# DC28_Jack-Attack_Badge-1.net
KiCad netlist of a schematic drawn in EAGLE
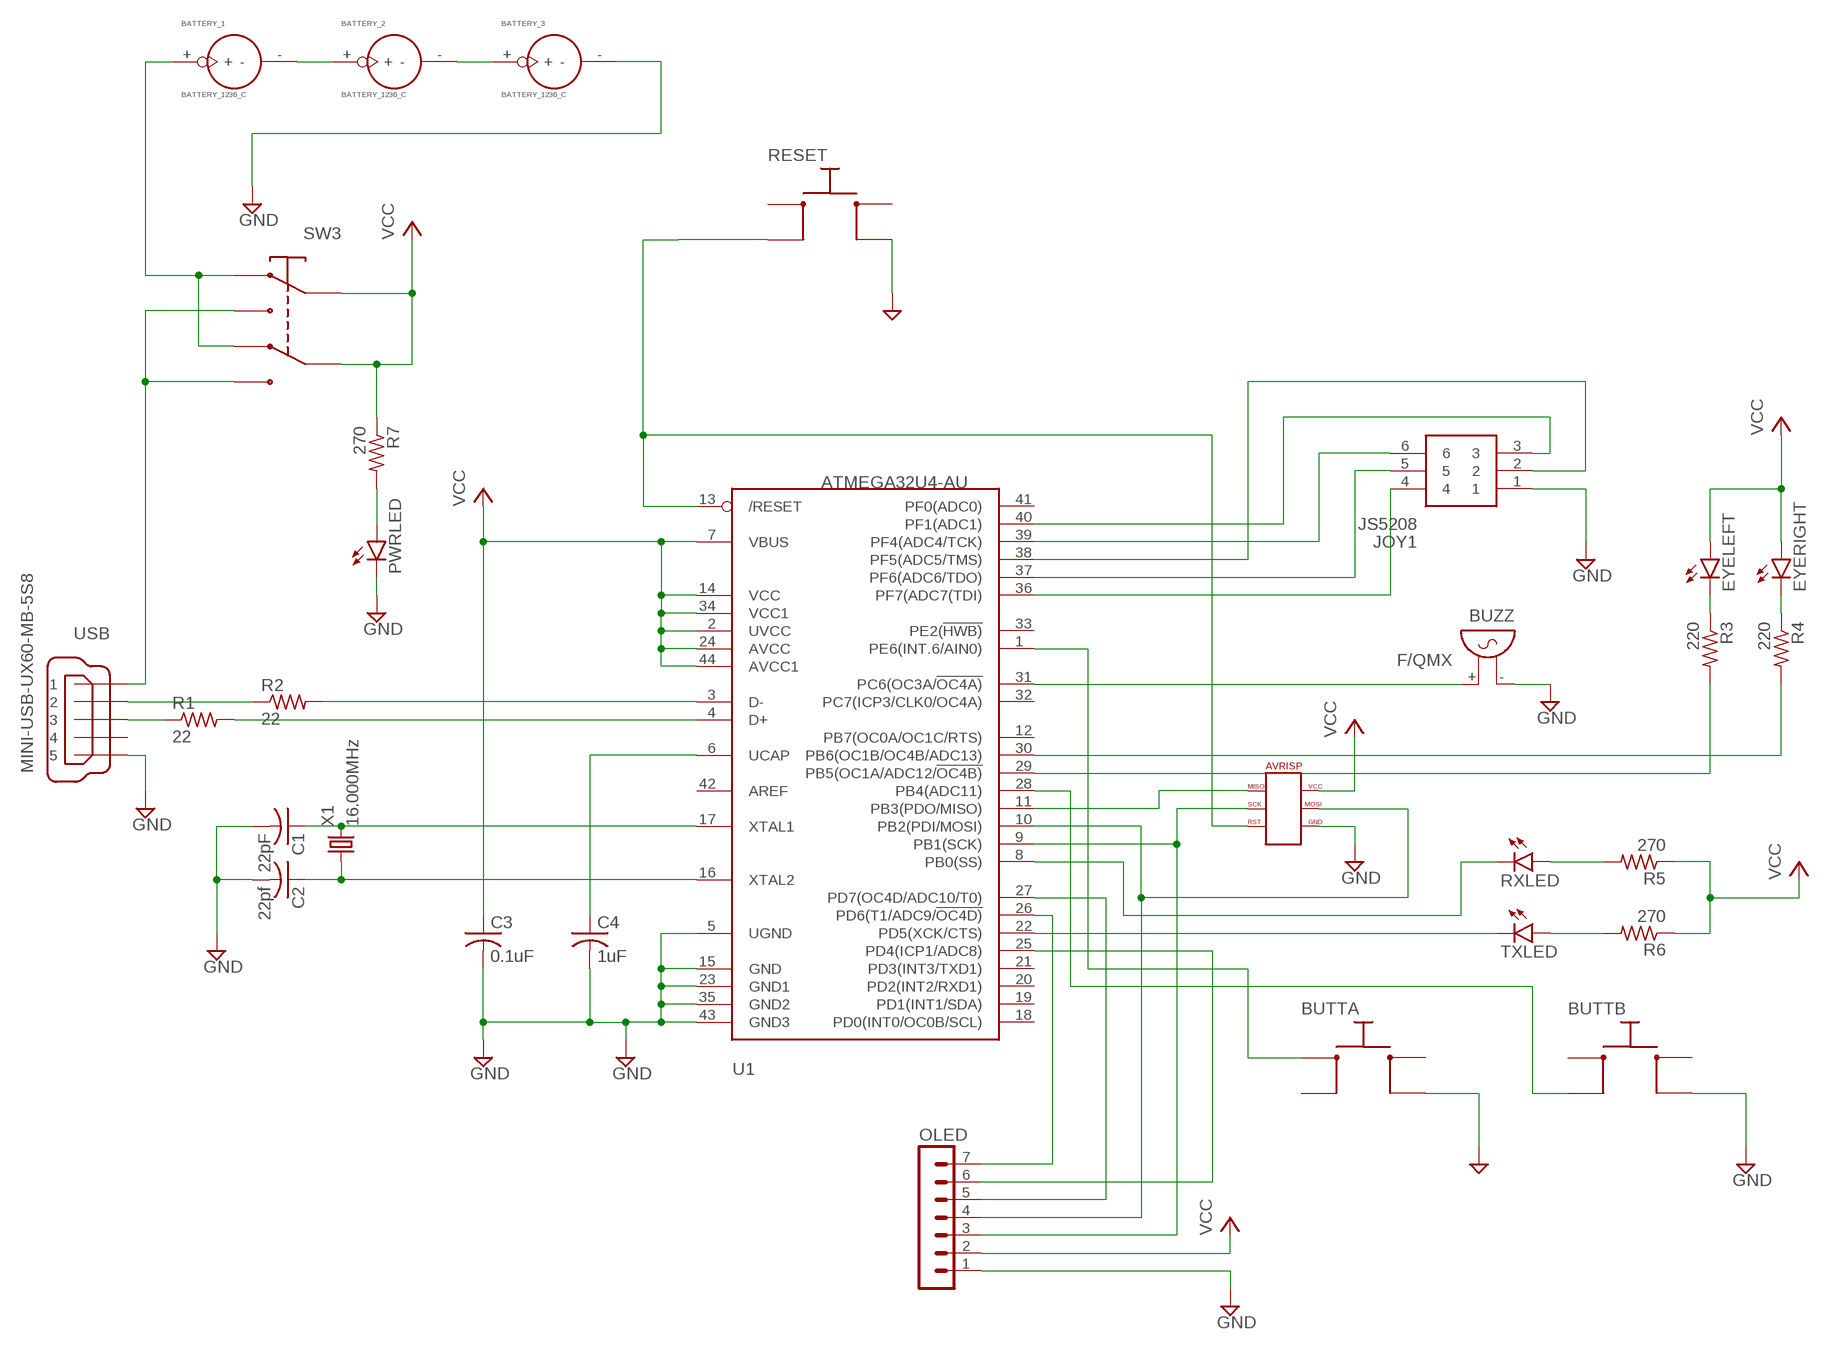
[diagram p0: schematic, sheet 1]

(export (version "E")
  (design (tool "Eeschema 10.0.6"))
  (components
    (comp (ref "BATTERY_1")
      (value "BATTERY_1236_C")
      (footprint "eagle-import:BATTERY_1236_C")
      (libsource (lib "eagle-import") (part "BATTERY_1236_C"))
    )
    (comp (ref "BATTERY_2")
      (value "BATTERY_1236_C")
      (footprint "eagle-import:BATTERY_1236_C")
      (libsource (lib "eagle-import") (part "BATTERY_1236_C"))
    )
    (comp (ref "BATTERY_3")
      (value "BATTERY_1236_C")
      (footprint "eagle-import:BATTERY_1236_C")
      (libsource (lib "eagle-import") (part "BATTERY_1236_C"))
    )
    (comp (ref "BUTTA")
      (value "PTS645")
      (footprint "eagle-import:PTS645_SMD")
      (libsource (lib "eagle-import") (part "PTS645"))
    )
    (comp (ref "BUTTB")
      (value "PTS645")
      (footprint "eagle-import:PTS645_SMD")
      (libsource (lib "eagle-import") (part "PTS645"))
    )
    (comp (ref "BUZZ")
      (value "F/QMX")
      (footprint "eagle-import:F_QMX")
      (libsource (lib "eagle-import") (part "F/QMX"))
    )
    (comp (ref "C1")
      (value "22pF")
      (footprint "eagle-import:C0805")
      (libsource (lib "eagle-import") (part "C-USC0805"))
    )
    (comp (ref "C2")
      (value "22pf")
      (footprint "eagle-import:C0805")
      (libsource (lib "eagle-import") (part "C-USC0805"))
    )
    (comp (ref "C3")
      (value "0.1uF")
      (footprint "eagle-import:C0805")
      (libsource (lib "eagle-import") (part "C-USC0805"))
    )
    (comp (ref "C4")
      (value "1uF")
      (footprint "eagle-import:C0805")
      (libsource (lib "eagle-import") (part "C-USC0805"))
    )
    (comp (ref "EYELEFT")
      (value "LED5MM")
      (footprint "eagle-import:LED5MM")
      (libsource (lib "eagle-import") (part "LED5MM"))
    )
    (comp (ref "EYERIGHT")
      (value "LED5MM")
      (footprint "eagle-import:LED5MM")
      (libsource (lib "eagle-import") (part "LED5MM"))
    )
    (comp (ref "JOY1")
      (value "JS5208")
      (footprint "eagle-import:JS5208")
      (fields (field (name "MOUSER_PART_NUMBER") "612-JS5208"))
      (libsource (lib "eagle-import") (part "JS5208"))
    )
    (comp (ref "OLED")
      (value "MA07-1")
      (footprint "eagle-import:MA07-1")
      (libsource (lib "eagle-import") (part "MA07-1"))
    )
    (comp (ref "PWRLED")
      (value "LEDCHIP-LED0805")
      (footprint "eagle-import:CHIP-LED0805")
      (libsource (lib "eagle-import") (part "LEDCHIP-LED0805"))
    )
    (comp (ref "R1")
      (value "22")
      (footprint "eagle-import:R0805")
      (libsource (lib "eagle-import") (part "R-US_R0805"))
    )
    (comp (ref "R2")
      (value "22")
      (footprint "eagle-import:R0805")
      (libsource (lib "eagle-import") (part "R-US_R0805"))
    )
    (comp (ref "R3")
      (value "220")
      (footprint "eagle-import:R0805")
      (libsource (lib "eagle-import") (part "R-US_R0805"))
    )
    (comp (ref "R4")
      (value "220")
      (footprint "eagle-import:R0805")
      (libsource (lib "eagle-import") (part "R-US_R0805"))
    )
    (comp (ref "R5")
      (value "270")
      (footprint "eagle-import:R0805")
      (libsource (lib "eagle-import") (part "R-US_R0805"))
    )
    (comp (ref "R6")
      (value "270")
      (footprint "eagle-import:R0805")
      (libsource (lib "eagle-import") (part "R-US_R0805"))
    )
    (comp (ref "R7")
      (value "270")
      (footprint "eagle-import:R0805")
      (libsource (lib "eagle-import") (part "R-US_R0805"))
    )
    (comp (ref "RESET")
      (value "PTS645")
      (footprint "eagle-import:PTS645_SMD")
      (libsource (lib "eagle-import") (part "PTS645"))
    )
    (comp (ref "RXLED")
      (value "LEDCHIP-LED0805")
      (footprint "eagle-import:CHIP-LED0805")
      (libsource (lib "eagle-import") (part "LEDCHIP-LED0805"))
    )
    (comp (ref "SW3")
      (value "JS202011AQN")
      (footprint "eagle-import:JS202011AQN")
      (libsource (lib "eagle-import") (part "JS202011AQN"))
    )
    (comp (ref "TXLED")
      (value "LEDCHIP-LED0805")
      (footprint "eagle-import:CHIP-LED0805")
      (libsource (lib "eagle-import") (part "LEDCHIP-LED0805"))
    )
    (comp (ref "U$1")
      (value "AVRISP_POGO")
      (footprint "eagle-import:AVRISP_POGO")
      (libsource (lib "eagle-import") (part "AVRISP_POGO"))
    )
    (comp (ref "U1")
      (value "ATMEGA32U4-AU")
      (footprint "eagle-import:TQFP44")
      (libsource (lib "eagle-import") (part "ATMEGA32U4-AU"))
    )
    (comp (ref "USB")
      (value "MINI-USB-UX60-MB-5S8")
      (footprint "eagle-import:UX60-MB-5S8")
      (libsource (lib "eagle-import") (part "MINI-USB-UX60-MB-5S8"))
    )
    (comp (ref "X1")
      (value "16.000MHz")
      (footprint "eagle-import:CSM-7X-DU")
      (libsource (lib "eagle-import") (part "CSM-7X-DU"))
    )
  )
  (nets
    (net (code "1") (name "GND") (class "Default")
      (node (ref "BATTERY_3") (pin "-") (pinfunction "-_-") (pintype "bidirectional"))
      (node (ref "BUTTA") (pin "P$4") (pinfunction "4_P$4") (pintype "bidirectional"))
      (node (ref "BUTTB") (pin "P$4") (pinfunction "4_P$4") (pintype "bidirectional"))
      (node (ref "BUZZ") (pin "-") (pinfunction "1_-") (pintype "passive"))
      (node (ref "C1") (pin "2") (pinfunction "2_2") (pintype "passive"))
      (node (ref "C2") (pin "2") (pinfunction "2_2") (pintype "passive"))
      (node (ref "C3") (pin "2") (pinfunction "2_2") (pintype "passive"))
      (node (ref "C4") (pin "2") (pinfunction "2_2") (pintype "passive"))
      (node (ref "JOY1") (pin "1") (pinfunction "1_1") (pintype "bidirectional"))
      (node (ref "OLED") (pin "1") (pinfunction "1_1") (pintype "passive"))
      (node (ref "PWRLED") (pin "C") (pinfunction "C_C") (pintype "passive"))
      (node (ref "RESET") (pin "P$4") (pinfunction "4_P$4") (pintype "bidirectional"))
      (node (ref "U$1") (pin "P$6") (pinfunction "P$6_P$6") (pintype "bidirectional"))
      (node (ref "U$1") (pin "P$6B") (pinfunction "P$6_P$6B") (pintype "bidirectional"))
      (node (ref "U1") (pin "15") (pinfunction "GND_15") (pintype "bidirectional"))
      (node (ref "U1") (pin "23") (pinfunction "GND1_23") (pintype "bidirectional"))
      (node (ref "U1") (pin "35") (pinfunction "GND2_35") (pintype "bidirectional"))
      (node (ref "U1") (pin "43") (pinfunction "GND3_43") (pintype "bidirectional"))
      (node (ref "U1") (pin "5") (pinfunction "UGND_5") (pintype "bidirectional"))
      (node (ref "USB") (pin "5") (pinfunction "5_5") (pintype "input"))
    )
    (net (code "2") (name "Net-(BATTERY_1-Pad-)") (class "Default")
      (node (ref "BATTERY_1") (pin "-") (pinfunction "-_-") (pintype "bidirectional"))
      (node (ref "BATTERY_2") (pin "+") (pinfunction "+_+") (pintype "bidirectional"))
    )
    (net (code "3") (name "Net-(BATTERY_2-Pad-)") (class "Default")
      (node (ref "BATTERY_2") (pin "-") (pinfunction "-_-") (pintype "bidirectional"))
      (node (ref "BATTERY_3") (pin "+") (pinfunction "+_+") (pintype "bidirectional"))
    )
    (net (code "4") (name "Net-(BUTTA-1)") (class "Default")
      (node (ref "BUTTA") (pin "P$1") (pinfunction "1_P$1") (pintype "bidirectional"))
      (node (ref "U1") (pin "1") (pinfunction "PE6(INT.6/AIN0)_1") (pintype "bidirectional"))
    )
    (net (code "5") (name "Net-(BUTTB-2)") (class "Default")
      (node (ref "BUTTB") (pin "P$2") (pinfunction "2_P$2") (pintype "bidirectional"))
      (node (ref "U1") (pin "28") (pinfunction "PB4(ADC11)_28") (pintype "bidirectional"))
    )
    (net (code "6") (name "Net-(BUZZ-2)") (class "Default")
      (node (ref "BUZZ") (pin "+") (pinfunction "2_+") (pintype "passive"))
      (node (ref "U1") (pin "31") (pinfunction "PC6(OC3A/~{OC4A})_31") (pintype "bidirectional"))
    )
    (net (code "7") (name "Net-(EYELEFT-C)") (class "Default")
      (node (ref "EYELEFT") (pin "K") (pinfunction "C_K") (pintype "passive"))
      (node (ref "R3") (pin "1") (pinfunction "1_1") (pintype "passive"))
    )
    (net (code "8") (name "Net-(EYERIGHT-C)") (class "Default")
      (node (ref "EYERIGHT") (pin "K") (pinfunction "C_K") (pintype "passive"))
      (node (ref "R4") (pin "1") (pinfunction "1_1") (pintype "passive"))
    )
    (net (code "9") (name "Net-(PWRLED-PadA)") (class "Default")
      (node (ref "PWRLED") (pin "A") (pinfunction "A_A") (pintype "passive"))
      (node (ref "R7") (pin "2") (pinfunction "2_2") (pintype "passive"))
    )
    (net (code "10") (name "Net-(R1-Pad1)") (class "Default")
      (node (ref "R1") (pin "1") (pinfunction "1_1") (pintype "passive"))
      (node (ref "USB") (pin "3") (pinfunction "3_3") (pintype "input"))
    )
    (net (code "11") (name "Net-(R2-Pad1)") (class "Default")
      (node (ref "R2") (pin "1") (pinfunction "1_1") (pintype "passive"))
      (node (ref "USB") (pin "2") (pinfunction "2_2") (pintype "input"))
    )
    (net (code "12") (name "Net-(R5-Pad2)") (class "Default")
      (node (ref "R5") (pin "2") (pinfunction "2_2") (pintype "passive"))
      (node (ref "RXLED") (pin "A") (pinfunction "A_A") (pintype "passive"))
    )
    (net (code "13") (name "Net-(R6-Pad2)") (class "Default")
      (node (ref "R6") (pin "2") (pinfunction "2_2") (pintype "passive"))
      (node (ref "TXLED") (pin "A") (pinfunction "A_A") (pintype "passive"))
    )
    (net (code "14") (name "Net-(RESET-2)") (class "Default")
      (node (ref "RESET") (pin "P$2") (pinfunction "2_P$2") (pintype "bidirectional"))
      (node (ref "U$1") (pin "P$5") (pinfunction "P$5_P$5") (pintype "bidirectional"))
      (node (ref "U$1") (pin "P$5B") (pinfunction "P$5_P$5B") (pintype "bidirectional"))
      (node (ref "U1") (pin "13") (pinfunction "/RESET_13") (pintype "bidirectional"))
    )
    (net (code "15") (name "Net-(SW3-1)") (class "Default")
      (node (ref "BATTERY_1") (pin "+") (pinfunction "+_+") (pintype "bidirectional"))
      (node (ref "SW3") (pin "P$1") (pinfunction "1_P$1") (pintype "bidirectional"))
      (node (ref "SW3") (pin "P$4") (pinfunction "4_P$4") (pintype "bidirectional"))
    )
    (net (code "16") (name "Net-(SW3-3)") (class "Default")
      (node (ref "SW3") (pin "P$3") (pinfunction "3_P$3") (pintype "bidirectional"))
      (node (ref "SW3") (pin "P$6") (pinfunction "6_P$6") (pintype "bidirectional"))
      (node (ref "USB") (pin "1") (pinfunction "1_1") (pintype "input"))
    )
    (net (code "17") (name "Net-(U1-D+)") (class "Default")
      (node (ref "R1") (pin "2") (pinfunction "2_2") (pintype "passive"))
      (node (ref "U1") (pin "4") (pinfunction "D+_4") (pintype "bidirectional"))
    )
    (net (code "18") (name "Net-(U1-D-)") (class "Default")
      (node (ref "R2") (pin "2") (pinfunction "2_2") (pintype "passive"))
      (node (ref "U1") (pin "3") (pinfunction "D-_3") (pintype "bidirectional"))
    )
    (net (code "19") (name "Net-(U1-PB0(SS))") (class "Default")
      (node (ref "RXLED") (pin "C") (pinfunction "C_C") (pintype "passive"))
      (node (ref "U1") (pin "8") (pinfunction "PB0(SS)_8") (pintype "bidirectional"))
    )
    (net (code "20") (name "Net-(U1-PB1(SCK))") (class "Default")
      (node (ref "OLED") (pin "3") (pinfunction "3_3") (pintype "passive"))
      (node (ref "U$1") (pin "P$3") (pinfunction "P$3_P$3") (pintype "bidirectional"))
      (node (ref "U$1") (pin "P$3B") (pinfunction "P$3_P$3B") (pintype "bidirectional"))
      (node (ref "U1") (pin "9") (pinfunction "PB1(SCK)_9") (pintype "bidirectional"))
    )
    (net (code "21") (name "Net-(U1-PB2(PDI{slash}MOSI))") (class "Default")
      (node (ref "OLED") (pin "4") (pinfunction "4_4") (pintype "passive"))
      (node (ref "U$1") (pin "P$4") (pinfunction "P$4_P$4") (pintype "bidirectional"))
      (node (ref "U$1") (pin "P$4B") (pinfunction "P$4_P$4B") (pintype "bidirectional"))
      (node (ref "U1") (pin "10") (pinfunction "PB2(PDI/MOSI)_10") (pintype "bidirectional"))
    )
    (net (code "22") (name "Net-(U1-PB3(PDO{slash}MISO))") (class "Default")
      (node (ref "U$1") (pin "P$1") (pinfunction "P$1_P$1") (pintype "bidirectional"))
      (node (ref "U$1") (pin "P$1B") (pinfunction "P$1_P$1B") (pintype "bidirectional"))
      (node (ref "U1") (pin "11") (pinfunction "PB3(PDO/MISO)_11") (pintype "bidirectional"))
    )
    (net (code "23") (name "Net-(U1-PB5(OC1A{slash}ADC12{slash}~{OC4B}))") (class "Default")
      (node (ref "R3") (pin "2") (pinfunction "2_2") (pintype "passive"))
      (node (ref "U1") (pin "29") (pinfunction "PB5(OC1A/ADC12/~{OC4B})_29") (pintype "bidirectional"))
    )
    (net (code "24") (name "Net-(U1-PB6(OC1B{slash}OC4B{slash}ADC13))") (class "Default")
      (node (ref "R4") (pin "2") (pinfunction "2_2") (pintype "passive"))
      (node (ref "U1") (pin "30") (pinfunction "PB6(OC1B/OC4B/ADC13)_30") (pintype "bidirectional"))
    )
    (net (code "25") (name "Net-(U1-PD4(ICP1{slash}ADC8))") (class "Default")
      (node (ref "OLED") (pin "6") (pinfunction "6_6") (pintype "passive"))
      (node (ref "U1") (pin "25") (pinfunction "PD4(ICP1/ADC8)_25") (pintype "bidirectional"))
    )
    (net (code "26") (name "Net-(U1-PD5(XCK{slash}CTS))") (class "Default")
      (node (ref "TXLED") (pin "C") (pinfunction "C_C") (pintype "passive"))
      (node (ref "U1") (pin "22") (pinfunction "PD5(XCK/CTS)_22") (pintype "bidirectional"))
    )
    (net (code "27") (name "Net-(U1-PD6(T1{slash}ADC9{slash}~{OC4D}))") (class "Default")
      (node (ref "OLED") (pin "7") (pinfunction "7_7") (pintype "passive"))
      (node (ref "U1") (pin "26") (pinfunction "PD6(T1/ADC9/~{OC4D})_26") (pintype "bidirectional"))
    )
    (net (code "28") (name "Net-(U1-PD7(OC4D{slash}ADC10{slash}T0))") (class "Default")
      (node (ref "OLED") (pin "5") (pinfunction "5_5") (pintype "passive"))
      (node (ref "U1") (pin "27") (pinfunction "PD7(OC4D/ADC10/T0)_27") (pintype "bidirectional"))
    )
    (net (code "29") (name "Net-(U1-PF1(ADC1))") (class "Default")
      (node (ref "JOY1") (pin "3") (pinfunction "3_3") (pintype "bidirectional"))
      (node (ref "U1") (pin "40") (pinfunction "PF1(ADC1)_40") (pintype "bidirectional"))
    )
    (net (code "30") (name "Net-(U1-PF4(ADC4{slash}TCK))") (class "Default")
      (node (ref "JOY1") (pin "6") (pinfunction "6_6") (pintype "bidirectional"))
      (node (ref "U1") (pin "39") (pinfunction "PF4(ADC4/TCK)_39") (pintype "bidirectional"))
    )
    (net (code "31") (name "Net-(U1-PF5(ADC5{slash}TMS))") (class "Default")
      (node (ref "JOY1") (pin "2") (pinfunction "2_2") (pintype "bidirectional"))
      (node (ref "U1") (pin "38") (pinfunction "PF5(ADC5/TMS)_38") (pintype "bidirectional"))
    )
    (net (code "32") (name "Net-(U1-PF6(ADC6{slash}TDO))") (class "Default")
      (node (ref "JOY1") (pin "5") (pinfunction "5_5") (pintype "bidirectional"))
      (node (ref "U1") (pin "37") (pinfunction "PF6(ADC6/TDO)_37") (pintype "bidirectional"))
    )
    (net (code "33") (name "Net-(U1-PF7(ADC7(TDI))") (class "Default")
      (node (ref "JOY1") (pin "4") (pinfunction "4_4") (pintype "bidirectional"))
      (node (ref "U1") (pin "36") (pinfunction "PF7(ADC7(TDI)_36") (pintype "bidirectional"))
    )
    (net (code "34") (name "Net-(U1-UCAP)") (class "Default")
      (node (ref "C4") (pin "1") (pinfunction "1_1") (pintype "passive"))
      (node (ref "U1") (pin "6") (pinfunction "UCAP_6") (pintype "bidirectional"))
    )
    (net (code "35") (name "Net-(U1-XTAL1)") (class "Default")
      (node (ref "C1") (pin "1") (pinfunction "1_1") (pintype "passive"))
      (node (ref "U1") (pin "17") (pinfunction "XTAL1_17") (pintype "bidirectional"))
      (node (ref "X1") (pin "2") (pinfunction "2_2") (pintype "passive"))
    )
    (net (code "36") (name "Net-(U1-XTAL2)") (class "Default")
      (node (ref "C2") (pin "1") (pinfunction "1_1") (pintype "passive"))
      (node (ref "U1") (pin "16") (pinfunction "XTAL2_16") (pintype "bidirectional"))
      (node (ref "X1") (pin "1") (pinfunction "1_1") (pintype "passive"))
    )
    (net (code "37") (name "VCC") (class "Default")
      (node (ref "C3") (pin "1") (pinfunction "1_1") (pintype "passive"))
      (node (ref "EYELEFT") (pin "A") (pinfunction "A_A") (pintype "passive"))
      (node (ref "EYERIGHT") (pin "A") (pinfunction "A_A") (pintype "passive"))
      (node (ref "OLED") (pin "2") (pinfunction "2_2") (pintype "passive"))
      (node (ref "R5") (pin "1") (pinfunction "1_1") (pintype "passive"))
      (node (ref "R6") (pin "1") (pinfunction "1_1") (pintype "passive"))
      (node (ref "R7") (pin "1") (pinfunction "1_1") (pintype "passive"))
      (node (ref "SW3") (pin "P$2") (pinfunction "2_P$2") (pintype "bidirectional"))
      (node (ref "SW3") (pin "P$5") (pinfunction "5_P$5") (pintype "bidirectional"))
      (node (ref "U$1") (pin "P$2") (pinfunction "P$2_P$2") (pintype "bidirectional"))
      (node (ref "U$1") (pin "P$2B") (pinfunction "P$2_P$2B") (pintype "bidirectional"))
      (node (ref "U1") (pin "14") (pinfunction "VCC_14") (pintype "bidirectional"))
      (node (ref "U1") (pin "2") (pinfunction "UVCC_2") (pintype "bidirectional"))
      (node (ref "U1") (pin "24") (pinfunction "AVCC_24") (pintype "bidirectional"))
      (node (ref "U1") (pin "34") (pinfunction "VCC1_34") (pintype "bidirectional"))
      (node (ref "U1") (pin "44") (pinfunction "AVCC1_44") (pintype "bidirectional"))
      (node (ref "U1") (pin "7") (pinfunction "VBUS_7") (pintype "bidirectional"))
    )
    (net (code "38") (name "unconnected-(BUTTA-2-PadP$2)") (class "Default")
      (node (ref "BUTTA") (pin "P$2") (pinfunction "2_P$2") (pintype "bidirectional"))
    )
    (net (code "39") (name "unconnected-(BUTTA-3-PadP$3)") (class "Default")
      (node (ref "BUTTA") (pin "P$3") (pinfunction "3_P$3") (pintype "bidirectional"))
    )
    (net (code "40") (name "unconnected-(BUTTB-1-PadP$1)") (class "Default")
      (node (ref "BUTTB") (pin "P$1") (pinfunction "1_P$1") (pintype "bidirectional"))
    )
    (net (code "41") (name "unconnected-(BUTTB-3-PadP$3)") (class "Default")
      (node (ref "BUTTB") (pin "P$3") (pinfunction "3_P$3") (pintype "bidirectional"))
    )
    (net (code "42") (name "unconnected-(RESET-1-PadP$1)") (class "Default")
      (node (ref "RESET") (pin "P$1") (pinfunction "1_P$1") (pintype "bidirectional"))
    )
    (net (code "43") (name "unconnected-(RESET-3-PadP$3)") (class "Default")
      (node (ref "RESET") (pin "P$3") (pinfunction "3_P$3") (pintype "bidirectional"))
    )
    (net (code "44") (name "unconnected-(U1-AREF-Pad42)") (class "Default")
      (node (ref "U1") (pin "42") (pinfunction "AREF_42") (pintype "bidirectional"))
    )
    (net (code "45") (name "unconnected-(U1-PB7(OC0A{slash}OC1C{slash}RTS)-Pad12)") (class "Default")
      (node (ref "U1") (pin "12") (pinfunction "PB7(OC0A/OC1C/RTS)_12") (pintype "bidirectional"))
    )
    (net (code "46") (name "unconnected-(U1-PC7(ICP3{slash}CLK0{slash}OC4A)-Pad32)") (class "Default")
      (node (ref "U1") (pin "32") (pinfunction "PC7(ICP3/CLK0/OC4A)_32") (pintype "bidirectional"))
    )
    (net (code "47") (name "unconnected-(U1-PD0(INT0{slash}OC0B{slash}SCL)-Pad18)") (class "Default")
      (node (ref "U1") (pin "18") (pinfunction "PD0(INT0/OC0B/SCL)_18") (pintype "bidirectional"))
    )
    (net (code "48") (name "unconnected-(U1-PD1(INT1{slash}SDA)-Pad19)") (class "Default")
      (node (ref "U1") (pin "19") (pinfunction "PD1(INT1/SDA)_19") (pintype "bidirectional"))
    )
    (net (code "49") (name "unconnected-(U1-PD2(INT2{slash}RXD1)-Pad20)") (class "Default")
      (node (ref "U1") (pin "20") (pinfunction "PD2(INT2/RXD1)_20") (pintype "bidirectional"))
    )
    (net (code "50") (name "unconnected-(U1-PD3(INT3{slash}TXD1)-Pad21)") (class "Default")
      (node (ref "U1") (pin "21") (pinfunction "PD3(INT3/TXD1)_21") (pintype "bidirectional"))
    )
    (net (code "51") (name "unconnected-(U1-PE2(~{HWB})-Pad33)") (class "Default")
      (node (ref "U1") (pin "33") (pinfunction "PE2(~{HWB})_33") (pintype "bidirectional"))
    )
    (net (code "52") (name "unconnected-(U1-PF0(ADC0)-Pad41)") (class "Default")
      (node (ref "U1") (pin "41") (pinfunction "PF0(ADC0)_41") (pintype "bidirectional"))
    )
    (net (code "53") (name "unconnected-(USB-Pad4)") (class "Default")
      (node (ref "USB") (pin "4") (pinfunction "4_4") (pintype "input"))
    )
  )
)
